# STM32F103C8T6.net
KiCad netlist of a schematic drawn in Altium Designer
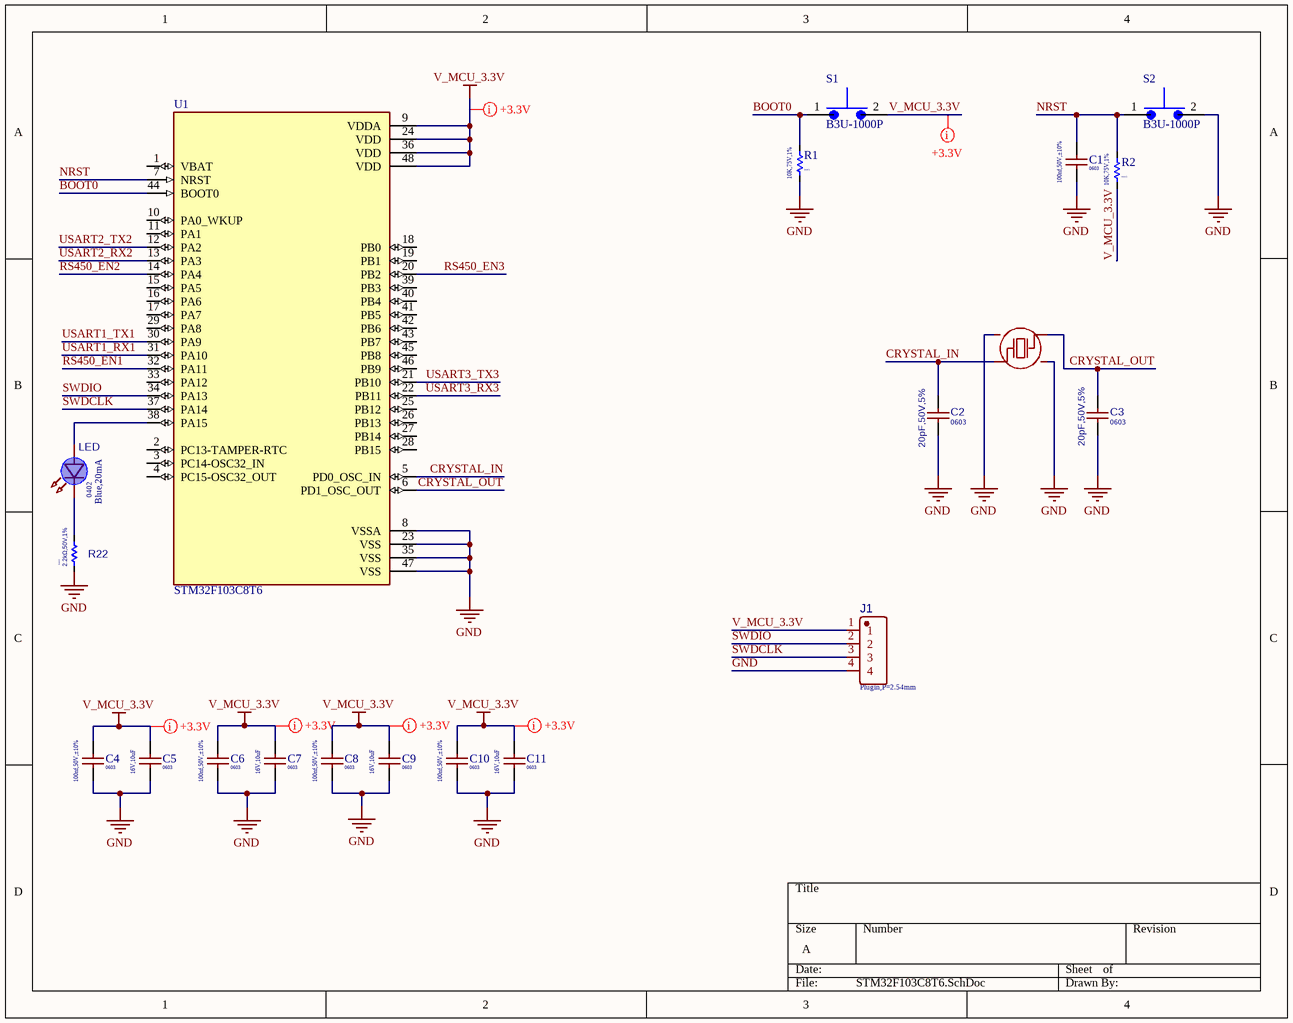
[diagram p0: STM32F103C8T6.SchDoc]

(export (version "E")
  (design (tool "Eeschema 10.0.6"))
  (components
    (comp (ref "C1")
      (value "100nf,50V,±10%")
      (footprint "C0603")
      (description "50V 100nF X7R ±10% 0603 Multilayer Ceramic Capacitors MLCC - SMD/SMT ROHS")
      (fields
        (field (name "MPN") "603-CC603KRX7R9BB104")
        (field (name "MANUFACTURER") "KEMET")
        (field (name "PACKAGE") "0603")
      )
      (libsource (lib "RCL") (part "CC0603KRX7R9BB104"))
    )
    (comp (ref "C2")
      (value "20pF,50V,5%")
      (footprint "C0603")
      (description "50V 20pF C0G ±5% 0603 Multilayer Ceramic Capacitors MLCC - SMD/SMT ROHS")
      (fields
        (field (name "MANUFACTURER") "SHOU HAN")
        (field (name "MPN") "CL10C200JB8NNNC")
        (field (name "PACKAGE") "0603")
      )
      (libsource (lib "RCL") (part "CL10C200JB8NNNC"))
    )
    (comp (ref "C3")
      (value "20pF,50V,5%")
      (footprint "C0603")
      (description "50V 20pF C0G ±5% 0603 Multilayer Ceramic Capacitors MLCC - SMD/SMT ROHS")
      (fields
        (field (name "MANUFACTURER") "SHOU HAN")
        (field (name "MPN") "CL10C200JB8NNNC")
        (field (name "PACKAGE") "0603")
      )
      (libsource (lib "RCL") (part "CL10C200JB8NNNC"))
    )
    (comp (ref "C4")
      (value "100nf,50V,±10%")
      (footprint "C0603")
      (description "50V 100nF X7R ±10% 0603 Multilayer Ceramic Capacitors MLCC - SMD/SMT ROHS")
      (fields
        (field (name "MPN") "603-CC603KRX7R9BB104")
        (field (name "MANUFACTURER") "KEMET")
        (field (name "PACKAGE") "0603")
      )
      (libsource (lib "RCL") (part "CC0603KRX7R9BB104"))
    )
    (comp (ref "C5")
      (value "16V,10uF")
      (footprint "CAPC1608X90N")
      (description "16V 10uF Y5V ±20% 0603 Multilayer Ceramic Capacitors MLCC - SMD/SMT ROHS")
      (fields
        (field (name "MANUFACTURER") "KEMET")
        (field (name "MPN") "CC0603KRX7R9BB104")
        (field (name "PACKAGE") "0603")
      )
      (libsource (lib "RCL") (part "0603F106M160NT"))
    )
    (comp (ref "C6")
      (value "100nf,50V,±10%")
      (footprint "C0603")
      (description "50V 100nF X7R ±10% 0603 Multilayer Ceramic Capacitors MLCC - SMD/SMT ROHS")
      (fields
        (field (name "MPN") "603-CC603KRX7R9BB104")
        (field (name "MANUFACTURER") "KEMET")
        (field (name "PACKAGE") "0603")
      )
      (libsource (lib "RCL") (part "CC0603KRX7R9BB104"))
    )
    (comp (ref "C7")
      (value "16V,10uF")
      (footprint "CAPC1608X90N")
      (description "16V 10uF Y5V ±20% 0603 Multilayer Ceramic Capacitors MLCC - SMD/SMT ROHS")
      (fields
        (field (name "MANUFACTURER") "KEMET")
        (field (name "MPN") "CC0603KRX7R9BB104")
        (field (name "PACKAGE") "0603")
      )
      (libsource (lib "RCL") (part "0603F106M160NT"))
    )
    (comp (ref "C8")
      (value "100nf,50V,±10%")
      (footprint "C0603")
      (description "50V 100nF X7R ±10% 0603 Multilayer Ceramic Capacitors MLCC - SMD/SMT ROHS")
      (fields
        (field (name "MPN") "603-CC603KRX7R9BB104")
        (field (name "MANUFACTURER") "KEMET")
        (field (name "PACKAGE") "0603")
      )
      (libsource (lib "RCL") (part "CC0603KRX7R9BB104"))
    )
    (comp (ref "C9")
      (value "16V,10uF")
      (footprint "CAPC1608X90N")
      (description "16V 10uF Y5V ±20% 0603 Multilayer Ceramic Capacitors MLCC - SMD/SMT ROHS")
      (fields
        (field (name "MANUFACTURER") "KEMET")
        (field (name "MPN") "CC0603KRX7R9BB104")
        (field (name "PACKAGE") "0603")
      )
      (libsource (lib "RCL") (part "0603F106M160NT"))
    )
    (comp (ref "C10")
      (value "100nf,50V,±10%")
      (footprint "C0603")
      (description "50V 100nF X7R ±10% 0603 Multilayer Ceramic Capacitors MLCC - SMD/SMT ROHS")
      (fields
        (field (name "MPN") "603-CC603KRX7R9BB104")
        (field (name "MANUFACTURER") "KEMET")
        (field (name "PACKAGE") "0603")
      )
      (libsource (lib "RCL") (part "CC0603KRX7R9BB104"))
    )
    (comp (ref "C11")
      (value "16V,10uF")
      (footprint "CAPC1608X90N")
      (description "16V 10uF Y5V ±20% 0603 Multilayer Ceramic Capacitors MLCC - SMD/SMT ROHS")
      (fields
        (field (name "MANUFACTURER") "KEMET")
        (field (name "MPN") "CC0603KRX7R9BB104")
        (field (name "PACKAGE") "0603")
      )
      (libsource (lib "RCL") (part "0603F106M160NT"))
    )
    (comp (ref "J1")
      (value "*")
      (footprint "PIN_4,P=2.54mm")
      (fields
        (field (name "MANUFACTURER") "XFCN")
        (field (name "MPN") "PZ254V-11-04P")
        (field (name "PACKAGE") "Plugin,P=2.54mm")
      )
      (libsource (lib "connector_button") (part "PZ254V-11-04P"))
    )
    (comp (ref "LED")
      (value "Blue,20mA")
      (footprint "LED 0402")
      (fields
        (field (name "MANUFACTURER") "XINGLIGHT")
        (field (name "MPN") "XL-1005UBC")
        (field (name "PACKAGE") "0402")
      )
      (libsource (lib "LED") (part "XL-1005UBC"))
    )
    (comp (ref "R1")
      (value "10K,75V,1%")
      (footprint "R0603")
      (description "100mW Thick Film Resistors ±100ppm/℃ ±1% 10kΩ 0603 Chip Resistor - Surface Mount ROHS")
      (fields
        (field (name "MPN") "0603WAF1002T5E")
        (field (name "MANUFACTURER") "UNI-ROYAL(Uniroyal Elec)")
        (field (name "PACKAGE") "0603")
      )
      (libsource (lib "RCL") (part "0603WAF1002T5E"))
    )
    (comp (ref "R2")
      (value "10K,75V,1%")
      (footprint "R0603")
      (description "100mW Thick Film Resistors ±100ppm/℃ ±1% 10kΩ 0603 Chip Resistor - Surface Mount ROHS")
      (fields
        (field (name "MPN") "0603WAF1002T5E")
        (field (name "MANUFACTURER") "UNI-ROYAL(Uniroyal Elec)")
        (field (name "PACKAGE") "0603")
      )
      (libsource (lib "RCL") (part "0603WAF1002T5E"))
    )
    (comp (ref "R22")
      (value "2.2kΩ,50V,1%")
      (footprint "R0402")
      (description "62.5mW Thick Film Resistors 50V ±100ppm/℃ ±1% 2.2kΩ 0402 Chip Resistor - Surface Mount ROHS")
      (fields
        (field (name "MPN") "RC0402FR-072K2L")
        (field (name "MANUFACTURER") "YAGEO")
        (field (name "PACKAGE") "0402")
      )
      (libsource (lib "RCL") (part "RC0402FR-072K2L"))
    )
    (comp (ref "S1")
      (value "B3U-1000P")
      (footprint "B3U-1000P")
      (description "2.5mm 1.6mm Round Button 50mA Brick nogging 3mm SPST 153gf 12V SMD,2.5x3mm Tactile Switches ROHS")
      (fields (field (name "MANUFACTURER") "Omron Electronics") (field (name "MPN") "653-B3U-1000P"))
      (libsource (lib "connector_button") (part "B3U-1000P"))
    )
    (comp (ref "S2")
      (value "B3U-1000P")
      (footprint "B3U-1000P")
      (description "2.5mm 1.6mm Round Button 50mA Brick nogging 3mm SPST 153gf 12V SMD,2.5x3mm Tactile Switches ROHS")
      (fields (field (name "MANUFACTURER") "Omron Electronics") (field (name "MPN") "653-B3U-1000P"))
      (libsource (lib "connector_button") (part "B3U-1000P"))
    )
    (comp (ref "U1")
      (value "STM32F103C8T6")
      (footprint "STM32F103C8T6")
      (fields (field (name "MANUFACTURER") "STMicroelectronics"))
      (libsource (lib "IC") (part "STM32F103C8T6"))
    )
    (comp (ref "X1")
      (value "8MHz")
      (footprint "SMD3225-4P")
      (description "8MHz Surface Mount Crystal 20pF ±10ppm ±20ppm SMD3225-4P Crystals ROHS")
      (fields (field (name "MANUFACTURER") "YXC") (field (name "MPN") "X32258MSB4SI"))
      (libsource (lib "RCL") (part "X32258MSB4SI"))
    )
  )
  (nets
    (net (code "1") (name "/BOOT0") (class "Default")
      (node (ref "R1") (pin "1") (pinfunction "1_1") (pintype "passive"))
      (node (ref "S1") (pin "1") (pinfunction "1_1") (pintype "passive"))
      (node (ref "U1") (pin "44") (pinfunction "BOOT0_44") (pintype "input"))
    )
    (net (code "2") (name "/CRYSTAL_IN") (class "Default")
      (node (ref "C2") (pin "2") (pinfunction "2_2") (pintype "passive"))
      (node (ref "U1") (pin "5") (pinfunction "PD0_OSC_IN_5") (pintype "bidirectional"))
      (node (ref "X1") (pin "1") (pinfunction "1_1") (pintype "passive"))
    )
    (net (code "3") (name "/CRYSTAL_OUT") (class "Default")
      (node (ref "C3") (pin "2") (pinfunction "2_2") (pintype "passive"))
      (node (ref "U1") (pin "6") (pinfunction "PD1_OSC_OUT_6") (pintype "bidirectional"))
      (node (ref "X1") (pin "3") (pinfunction "3_3") (pintype "passive"))
    )
    (net (code "4") (name "/NRST") (class "Default")
      (node (ref "C1") (pin "2") (pinfunction "2_2") (pintype "passive"))
      (node (ref "R2") (pin "1") (pinfunction "1_1") (pintype "passive"))
      (node (ref "S2") (pin "1") (pinfunction "1_1") (pintype "passive"))
      (node (ref "U1") (pin "7") (pinfunction "NRST_7") (pintype "input"))
    )
    (net (code "5") (name "/RS450_EN1") (class "Default")
      (node (ref "U1") (pin "32") (pinfunction "PA11_32") (pintype "bidirectional"))
    )
    (net (code "6") (name "/RS450_EN2") (class "Default")
      (node (ref "U1") (pin "14") (pinfunction "PA4_14") (pintype "bidirectional"))
    )
    (net (code "7") (name "/RS450_EN3") (class "Default")
      (node (ref "U1") (pin "20") (pinfunction "PB2_20") (pintype "bidirectional"))
    )
    (net (code "8") (name "/SWDCLK") (class "Default")
      (node (ref "J1") (pin "3") (pinfunction "3_3") (pintype "passive"))
      (node (ref "U1") (pin "37") (pinfunction "PA14_37") (pintype "bidirectional"))
    )
    (net (code "9") (name "/SWDIO") (class "Default")
      (node (ref "J1") (pin "2") (pinfunction "2_2") (pintype "passive"))
      (node (ref "U1") (pin "34") (pinfunction "PA13_34") (pintype "bidirectional"))
    )
    (net (code "10") (name "/USART1_RX1") (class "Default")
      (node (ref "U1") (pin "31") (pinfunction "PA10_31") (pintype "bidirectional"))
    )
    (net (code "11") (name "/USART1_TX1") (class "Default")
      (node (ref "U1") (pin "30") (pinfunction "PA9_30") (pintype "bidirectional"))
    )
    (net (code "12") (name "/USART2_RX2") (class "Default")
      (node (ref "U1") (pin "13") (pinfunction "PA3_13") (pintype "bidirectional"))
    )
    (net (code "13") (name "/USART2_TX2") (class "Default")
      (node (ref "U1") (pin "12") (pinfunction "PA2_12") (pintype "bidirectional"))
    )
    (net (code "14") (name "/USART3_RX3") (class "Default")
      (node (ref "U1") (pin "22") (pinfunction "PB11_22") (pintype "bidirectional"))
    )
    (net (code "15") (name "/USART3_TX3") (class "Default")
      (node (ref "U1") (pin "21") (pinfunction "PB10_21") (pintype "bidirectional"))
    )
    (net (code "16") (name "GND") (class "Default")
      (node (ref "C1") (pin "1") (pinfunction "1_1") (pintype "passive"))
      (node (ref "C10") (pin "1") (pinfunction "1_1") (pintype "passive"))
      (node (ref "C11") (pin "1") (pinfunction "1_1") (pintype "passive"))
      (node (ref "C2") (pin "1") (pinfunction "1_1") (pintype "passive"))
      (node (ref "C3") (pin "1") (pinfunction "1_1") (pintype "passive"))
      (node (ref "C4") (pin "1") (pinfunction "1_1") (pintype "passive"))
      (node (ref "C5") (pin "1") (pinfunction "1_1") (pintype "passive"))
      (node (ref "C6") (pin "1") (pinfunction "1_1") (pintype "passive"))
      (node (ref "C7") (pin "1") (pinfunction "1_1") (pintype "passive"))
      (node (ref "C8") (pin "1") (pinfunction "1_1") (pintype "passive"))
      (node (ref "C9") (pin "1") (pinfunction "1_1") (pintype "passive"))
      (node (ref "J1") (pin "4") (pinfunction "4_4") (pintype "passive"))
      (node (ref "R1") (pin "2") (pinfunction "2_2") (pintype "passive"))
      (node (ref "R22") (pin "1") (pinfunction "1_1") (pintype "passive"))
      (node (ref "S2") (pin "2") (pinfunction "2_2") (pintype "passive"))
      (node (ref "U1") (pin "23") (pinfunction "VSS_23") (pintype "power_in"))
      (node (ref "U1") (pin "35") (pinfunction "VSS_35") (pintype "power_in"))
      (node (ref "U1") (pin "47") (pinfunction "VSS_47") (pintype "power_in"))
      (node (ref "U1") (pin "8") (pinfunction "VSSA_8") (pintype "power_in"))
      (node (ref "X1") (pin "2") (pinfunction "2_2") (pintype "passive"))
      (node (ref "X1") (pin "4") (pinfunction "4_4") (pintype "passive"))
    )
    (net (code "17") (name "Net-(LED-A)") (class "Default")
      (node (ref "LED") (pin "2") (pinfunction "A_2") (pintype "passive"))
      (node (ref "U1") (pin "38") (pinfunction "PA15_38") (pintype "bidirectional"))
    )
    (net (code "18") (name "Net-(LED-K)") (class "Default")
      (node (ref "LED") (pin "1") (pinfunction "K_1") (pintype "passive"))
      (node (ref "R22") (pin "2") (pinfunction "2_2") (pintype "passive"))
    )
    (net (code "19") (name "V_MCU_3.3V") (class "Default")
      (node (ref "C10") (pin "2") (pinfunction "2_2") (pintype "passive"))
      (node (ref "C11") (pin "2") (pinfunction "2_2") (pintype "passive"))
      (node (ref "C4") (pin "2") (pinfunction "2_2") (pintype "passive"))
      (node (ref "C5") (pin "2") (pinfunction "2_2") (pintype "passive"))
      (node (ref "C6") (pin "2") (pinfunction "2_2") (pintype "passive"))
      (node (ref "C7") (pin "2") (pinfunction "2_2") (pintype "passive"))
      (node (ref "C8") (pin "2") (pinfunction "2_2") (pintype "passive"))
      (node (ref "C9") (pin "2") (pinfunction "2_2") (pintype "passive"))
      (node (ref "J1") (pin "1") (pinfunction "1_1") (pintype "passive"))
      (node (ref "R2") (pin "2") (pinfunction "2_2") (pintype "passive"))
      (node (ref "S1") (pin "2") (pinfunction "2_2") (pintype "passive"))
      (node (ref "U1") (pin "24") (pinfunction "VDD_24") (pintype "power_in"))
      (node (ref "U1") (pin "36") (pinfunction "VDD_36") (pintype "power_in"))
      (node (ref "U1") (pin "48") (pinfunction "VDD_48") (pintype "power_in"))
      (node (ref "U1") (pin "9") (pinfunction "VDDA_9") (pintype "power_in"))
    )
    (net (code "20") (name "unconnected-(U1-PA0_WKUP-Pad10)") (class "Default")
      (node (ref "U1") (pin "10") (pinfunction "PA0_WKUP_10") (pintype "bidirectional"))
    )
    (net (code "21") (name "unconnected-(U1-PA1-Pad11)") (class "Default")
      (node (ref "U1") (pin "11") (pinfunction "PA1_11") (pintype "bidirectional"))
    )
    (net (code "22") (name "unconnected-(U1-PA5-Pad15)") (class "Default")
      (node (ref "U1") (pin "15") (pinfunction "PA5_15") (pintype "bidirectional"))
    )
    (net (code "23") (name "unconnected-(U1-PA6-Pad16)") (class "Default")
      (node (ref "U1") (pin "16") (pinfunction "PA6_16") (pintype "bidirectional"))
    )
    (net (code "24") (name "unconnected-(U1-PA7-Pad17)") (class "Default")
      (node (ref "U1") (pin "17") (pinfunction "PA7_17") (pintype "bidirectional"))
    )
    (net (code "25") (name "unconnected-(U1-PA8-Pad29)") (class "Default")
      (node (ref "U1") (pin "29") (pinfunction "PA8_29") (pintype "bidirectional"))
    )
    (net (code "26") (name "unconnected-(U1-PA12-Pad33)") (class "Default")
      (node (ref "U1") (pin "33") (pinfunction "PA12_33") (pintype "bidirectional"))
    )
    (net (code "27") (name "unconnected-(U1-PB0-Pad18)") (class "Default")
      (node (ref "U1") (pin "18") (pinfunction "PB0_18") (pintype "bidirectional"))
    )
    (net (code "28") (name "unconnected-(U1-PB1-Pad19)") (class "Default")
      (node (ref "U1") (pin "19") (pinfunction "PB1_19") (pintype "bidirectional"))
    )
    (net (code "29") (name "unconnected-(U1-PB3-Pad39)") (class "Default")
      (node (ref "U1") (pin "39") (pinfunction "PB3_39") (pintype "bidirectional"))
    )
    (net (code "30") (name "unconnected-(U1-PB4-Pad40)") (class "Default")
      (node (ref "U1") (pin "40") (pinfunction "PB4_40") (pintype "bidirectional"))
    )
    (net (code "31") (name "unconnected-(U1-PB5-Pad41)") (class "Default")
      (node (ref "U1") (pin "41") (pinfunction "PB5_41") (pintype "bidirectional"))
    )
    (net (code "32") (name "unconnected-(U1-PB6-Pad42)") (class "Default")
      (node (ref "U1") (pin "42") (pinfunction "PB6_42") (pintype "bidirectional"))
    )
    (net (code "33") (name "unconnected-(U1-PB7-Pad43)") (class "Default")
      (node (ref "U1") (pin "43") (pinfunction "PB7_43") (pintype "bidirectional"))
    )
    (net (code "34") (name "unconnected-(U1-PB8-Pad45)") (class "Default")
      (node (ref "U1") (pin "45") (pinfunction "PB8_45") (pintype "bidirectional"))
    )
    (net (code "35") (name "unconnected-(U1-PB9-Pad46)") (class "Default")
      (node (ref "U1") (pin "46") (pinfunction "PB9_46") (pintype "bidirectional"))
    )
    (net (code "36") (name "unconnected-(U1-PB12-Pad25)") (class "Default")
      (node (ref "U1") (pin "25") (pinfunction "PB12_25") (pintype "bidirectional"))
    )
    (net (code "37") (name "unconnected-(U1-PB13-Pad26)") (class "Default")
      (node (ref "U1") (pin "26") (pinfunction "PB13_26") (pintype "bidirectional"))
    )
    (net (code "38") (name "unconnected-(U1-PB14-Pad27)") (class "Default")
      (node (ref "U1") (pin "27") (pinfunction "PB14_27") (pintype "bidirectional"))
    )
    (net (code "39") (name "unconnected-(U1-PB15-Pad28)") (class "Default")
      (node (ref "U1") (pin "28") (pinfunction "PB15_28") (pintype "bidirectional"))
    )
    (net (code "40") (name "unconnected-(U1-PC13-TAMPER-RTC-Pad2)") (class "Default")
      (node (ref "U1") (pin "2") (pinfunction "PC13-TAMPER-RTC_2") (pintype "bidirectional"))
    )
    (net (code "41") (name "unconnected-(U1-PC14-OSC32_IN-Pad3)") (class "Default")
      (node (ref "U1") (pin "3") (pinfunction "PC14-OSC32_IN_3") (pintype "bidirectional"))
    )
    (net (code "42") (name "unconnected-(U1-PC15-OSC32_OUT-Pad4)") (class "Default")
      (node (ref "U1") (pin "4") (pinfunction "PC15-OSC32_OUT_4") (pintype "bidirectional"))
    )
    (net (code "43") (name "unconnected-(U1-VBAT-Pad1)") (class "Default")
      (node (ref "U1") (pin "1") (pinfunction "VBAT_1") (pintype "bidirectional"))
    )
  )
)
